# RC_Receive_SCH.net
KiCad netlist of a schematic drawn in Altium Designer
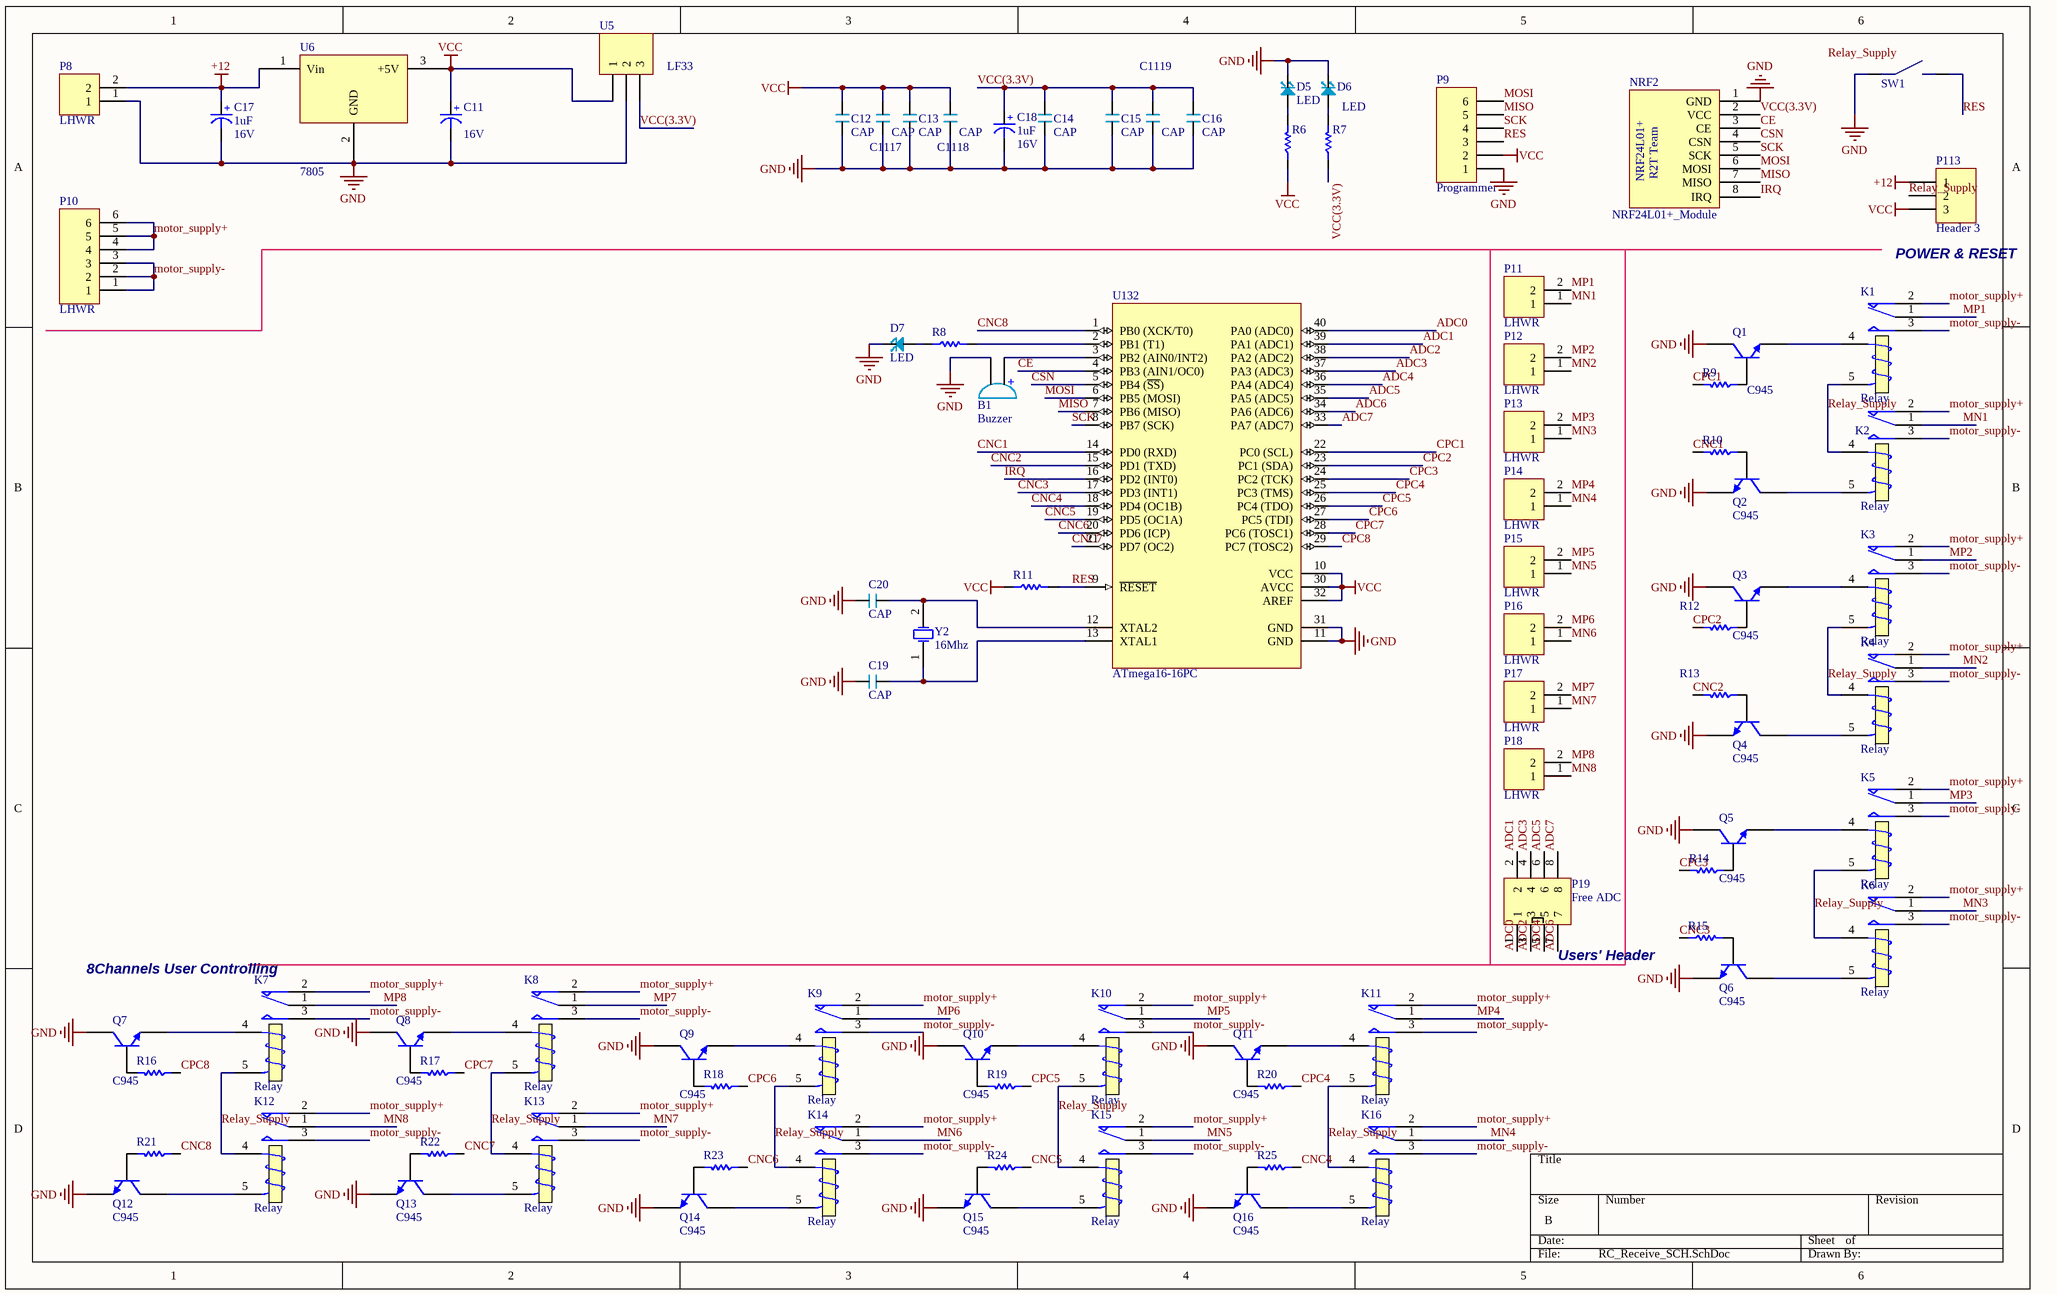
[diagram p0: RC_Receive_SCH.SchDoc]

(export (version "E")
  (design (tool "Eeschema 10.0.6"))
  (components
    (comp (ref "B1")
      (value "Buzzer")
      (footprint "Buzzer")
      (fields (field (name "DESIGNER") "Hamed Jafarzadeh"))
      (libsource (lib "R2T Team Library") (part "Buzzer"))
    )
    (comp (ref "C11")
      (value "~")
      (footprint "cap 01")
      (description "Polar Capacitor")
      (fields (field (name "VOLTAGE") "16V") (field (name "DESIGNER") "Saeid Jorablo"))
      (libsource (lib "My Library") (part "Cap-Polar"))
    )
    (comp (ref "C12") (value "CAP") (footprint "RAD_ADA") (libsource (lib "My_lib_new") (part "CAP")))
    (comp (ref "C13") (value "CAP") (footprint "RAD_ADA") (libsource (lib "My_lib_new") (part "CAP")))
    (comp (ref "C14") (value "CAP") (footprint "RAD_ADA") (libsource (lib "My_lib_new") (part "CAP")))
    (comp (ref "C15") (value "CAP") (footprint "RAD_ADA") (libsource (lib "My_lib_new") (part "CAP")))
    (comp (ref "C16") (value "CAP") (footprint "RAD_ADA") (libsource (lib "My_lib_new") (part "CAP")))
    (comp (ref "C17")
      (value "1uF")
      (footprint "cap 01")
      (description "Polar Capacitor")
      (fields (field (name "VOLTAGE") "16V") (field (name "DESIGNER") "Saeid Jorablo"))
      (libsource (lib "My Library") (part "Cap-Polar"))
    )
    (comp (ref "C18")
      (value "1uF")
      (footprint "cap 01")
      (description "Polar Capacitor")
      (fields (field (name "VOLTAGE") "16V") (field (name "DESIGNER") "Saeid Jorablo"))
      (libsource (lib "My Library") (part "Cap-Polar"))
    )
    (comp (ref "C19") (value "CAP") (footprint "RAD_ADA") (libsource (lib "My_lib_new") (part "CAP")))
    (comp (ref "C20") (value "CAP") (footprint "RAD_ADA") (libsource (lib "My_lib_new") (part "CAP")))
    (comp (ref "C1117") (value "CAP") (footprint "RAD_ADA") (libsource (lib "My_lib_new") (part "CAP")))
    (comp (ref "C1118") (value "CAP") (footprint "RAD_ADA") (libsource (lib "My_lib_new") (part "CAP")))
    (comp (ref "C1119") (value "CAP") (footprint "RAD_ADA") (libsource (lib "My_lib_new") (part "CAP")))
    (comp (ref "D5") (value "LED") (footprint "LED_5MM") (libsource (lib "My_lib_new") (part "LED")))
    (comp (ref "D6") (value "LED") (footprint "LED_5MM") (libsource (lib "My_lib_new") (part "LED")))
    (comp (ref "D7") (value "LED") (footprint "LED_5MM") (libsource (lib "My_lib_new") (part "LED")))
    (comp (ref "K1")
      (value "Relay")
      (footprint "Relay 15.40x12.10x13.10")
      (description "SPDT Relay")
      (fields (field (name "DESIGNER") "Eng. Saeid Jorablo"))
      (libsource (lib "My Library") (part "Relay"))
    )
    (comp (ref "K2")
      (value "Relay")
      (footprint "Relay 15.40x12.10x13.10")
      (description "SPDT Relay")
      (fields (field (name "DESIGNER") "Eng. Saeid Jorablo"))
      (libsource (lib "My Library") (part "Relay"))
    )
    (comp (ref "K3")
      (value "Relay")
      (footprint "Relay 15.40x12.10x13.10")
      (description "SPDT Relay")
      (fields (field (name "DESIGNER") "Eng. Saeid Jorablo"))
      (libsource (lib "My Library") (part "Relay"))
    )
    (comp (ref "K4")
      (value "Relay")
      (footprint "Relay 15.40x12.10x13.10")
      (description "SPDT Relay")
      (fields (field (name "DESIGNER") "Eng. Saeid Jorablo"))
      (libsource (lib "My Library") (part "Relay"))
    )
    (comp (ref "K5")
      (value "Relay")
      (footprint "Relay 15.40x12.10x13.10")
      (description "SPDT Relay")
      (fields (field (name "DESIGNER") "Eng. Saeid Jorablo"))
      (libsource (lib "My Library") (part "Relay"))
    )
    (comp (ref "K6")
      (value "Relay")
      (footprint "Relay 15.40x12.10x13.10")
      (description "SPDT Relay")
      (fields (field (name "DESIGNER") "Eng. Saeid Jorablo"))
      (libsource (lib "My Library") (part "Relay"))
    )
    (comp (ref "K7")
      (value "Relay")
      (footprint "Relay 15.40x12.10x13.10")
      (description "SPDT Relay")
      (fields (field (name "DESIGNER") "Eng. Saeid Jorablo"))
      (libsource (lib "My Library") (part "Relay"))
    )
    (comp (ref "K8")
      (value "Relay")
      (footprint "Relay 15.40x12.10x13.10")
      (description "SPDT Relay")
      (fields (field (name "DESIGNER") "Eng. Saeid Jorablo"))
      (libsource (lib "My Library") (part "Relay"))
    )
    (comp (ref "K9")
      (value "Relay")
      (footprint "Relay 15.40x12.10x13.10")
      (description "SPDT Relay")
      (fields (field (name "DESIGNER") "Eng. Saeid Jorablo"))
      (libsource (lib "My Library") (part "Relay"))
    )
    (comp (ref "K10")
      (value "Relay")
      (footprint "Relay 15.40x12.10x13.10")
      (description "SPDT Relay")
      (fields (field (name "DESIGNER") "Eng. Saeid Jorablo"))
      (libsource (lib "My Library") (part "Relay"))
    )
    (comp (ref "K11")
      (value "Relay")
      (footprint "Relay 15.40x12.10x13.10")
      (description "SPDT Relay")
      (fields (field (name "DESIGNER") "Eng. Saeid Jorablo"))
      (libsource (lib "My Library") (part "Relay"))
    )
    (comp (ref "K12")
      (value "Relay")
      (footprint "Relay 15.40x12.10x13.10")
      (description "SPDT Relay")
      (fields (field (name "DESIGNER") "Eng. Saeid Jorablo"))
      (libsource (lib "My Library") (part "Relay"))
    )
    (comp (ref "K13")
      (value "Relay")
      (footprint "Relay 15.40x12.10x13.10")
      (description "SPDT Relay")
      (fields (field (name "DESIGNER") "Eng. Saeid Jorablo"))
      (libsource (lib "My Library") (part "Relay"))
    )
    (comp (ref "K14")
      (value "Relay")
      (footprint "Relay 15.40x12.10x13.10")
      (description "SPDT Relay")
      (fields (field (name "DESIGNER") "Eng. Saeid Jorablo"))
      (libsource (lib "My Library") (part "Relay"))
    )
    (comp (ref "K15")
      (value "Relay")
      (footprint "Relay 15.40x12.10x13.10")
      (description "SPDT Relay")
      (fields (field (name "DESIGNER") "Eng. Saeid Jorablo"))
      (libsource (lib "My Library") (part "Relay"))
    )
    (comp (ref "K16")
      (value "Relay")
      (footprint "Relay 15.40x12.10x13.10")
      (description "SPDT Relay")
      (fields (field (name "DESIGNER") "Eng. Saeid Jorablo"))
      (libsource (lib "My Library") (part "Relay"))
    )
    (comp (ref "NRF2")
      (value "NRF24L01+_Module")
      (footprint "NRF24L01+_Module")
      (fields (field (name "DESIGNER:") "HamedJafarzadeh"))
      (libsource (lib "R2T Team Library") (part "NRF24L01+_Module"))
    )
    (comp (ref "P8")
      (value "LHWR")
      (footprint "Polarized Header 2")
      (fields (field (name "DESIGNER:") "Hamed Jafarzadeh - www.R2T.ir"))
      (libsource (lib "R2T Team Library") (part "2pin LHWR"))
    )
    (comp (ref "P9")
      (value "Programmer")
      (footprint "HDR1X6")
      (description "Header, 6-Pin")
      (fields (field (name "PUBLISHER") "Altium Limited"))
      (libsource (lib "Miscellaneous Connectors") (part "Header 6"))
    )
    (comp (ref "P10")
      (value "LHWR")
      (footprint "Polarized Header 6")
      (fields (field (name "DESIGNER:") "Hamed Jafarzadeh - www.R2T.ir"))
      (libsource (lib "R2T Team Library") (part "6pin LHWR"))
    )
    (comp (ref "P11")
      (value "LHWR")
      (footprint "Polarized Header 2")
      (fields (field (name "DESIGNER:") "Hamed Jafarzadeh - www.R2T.ir"))
      (libsource (lib "R2T Team Library") (part "2pin LHWR"))
    )
    (comp (ref "P12")
      (value "LHWR")
      (footprint "Polarized Header 2")
      (fields (field (name "DESIGNER:") "Hamed Jafarzadeh - www.R2T.ir"))
      (libsource (lib "R2T Team Library") (part "2pin LHWR"))
    )
    (comp (ref "P13")
      (value "LHWR")
      (footprint "Polarized Header 2")
      (fields (field (name "DESIGNER:") "Hamed Jafarzadeh - www.R2T.ir"))
      (libsource (lib "R2T Team Library") (part "2pin LHWR"))
    )
    (comp (ref "P14")
      (value "LHWR")
      (footprint "Polarized Header 2")
      (fields (field (name "DESIGNER:") "Hamed Jafarzadeh - www.R2T.ir"))
      (libsource (lib "R2T Team Library") (part "2pin LHWR"))
    )
    (comp (ref "P15")
      (value "LHWR")
      (footprint "Polarized Header 2")
      (fields (field (name "DESIGNER:") "Hamed Jafarzadeh - www.R2T.ir"))
      (libsource (lib "R2T Team Library") (part "2pin LHWR"))
    )
    (comp (ref "P16")
      (value "LHWR")
      (footprint "Polarized Header 2")
      (fields (field (name "DESIGNER:") "Hamed Jafarzadeh - www.R2T.ir"))
      (libsource (lib "R2T Team Library") (part "2pin LHWR"))
    )
    (comp (ref "P17")
      (value "LHWR")
      (footprint "Polarized Header 2")
      (fields (field (name "DESIGNER:") "Hamed Jafarzadeh - www.R2T.ir"))
      (libsource (lib "R2T Team Library") (part "2pin LHWR"))
    )
    (comp (ref "P18")
      (value "LHWR")
      (footprint "Polarized Header 2")
      (fields (field (name "DESIGNER:") "Hamed Jafarzadeh - www.R2T.ir"))
      (libsource (lib "R2T Team Library") (part "2pin LHWR"))
    )
    (comp (ref "P19")
      (value "Free ADC")
      (footprint "Box Header 2x4")
      (fields (field (name "DESIGNER") "HamedJafarzadeh - ww.R2T.ir"))
      (libsource (lib "R2T Team Library") (part "BoxHeader 2x4"))
    )
    (comp (ref "P113")
      (value "Header 3")
      (footprint "HDR1X3")
      (description "Header, 3-Pin")
      (fields (field (name "PUBLISHER") "Altium Limited"))
      (libsource (lib "Miscellaneous Connectors") (part "Header 3"))
    )
    (comp (ref "Q1")
      (value "C945")
      (footprint "C945")
      (description "NPN Transistor")
      (fields (field (name "DESIGNER") "Saeid Jorablo"))
      (libsource (lib "My Library") (part "C945"))
    )
    (comp (ref "Q2")
      (value "C945")
      (footprint "C945")
      (description "NPN Transistor")
      (fields (field (name "DESIGNER") "Saeid Jorablo"))
      (libsource (lib "My Library") (part "C945"))
    )
    (comp (ref "Q3")
      (value "C945")
      (footprint "C945")
      (description "NPN Transistor")
      (fields (field (name "DESIGNER") "Saeid Jorablo"))
      (libsource (lib "My Library") (part "C945"))
    )
    (comp (ref "Q4")
      (value "C945")
      (footprint "C945")
      (description "NPN Transistor")
      (fields (field (name "DESIGNER") "Saeid Jorablo"))
      (libsource (lib "My Library") (part "C945"))
    )
    (comp (ref "Q5")
      (value "C945")
      (footprint "C945")
      (description "NPN Transistor")
      (fields (field (name "DESIGNER") "Saeid Jorablo"))
      (libsource (lib "My Library") (part "C945"))
    )
    (comp (ref "Q6")
      (value "C945")
      (footprint "C945")
      (description "NPN Transistor")
      (fields (field (name "DESIGNER") "Saeid Jorablo"))
      (libsource (lib "My Library") (part "C945"))
    )
    (comp (ref "Q7")
      (value "C945")
      (footprint "C945")
      (description "NPN Transistor")
      (fields (field (name "DESIGNER") "Saeid Jorablo"))
      (libsource (lib "My Library") (part "C945"))
    )
    (comp (ref "Q8")
      (value "C945")
      (footprint "C945")
      (description "NPN Transistor")
      (fields (field (name "DESIGNER") "Saeid Jorablo"))
      (libsource (lib "My Library") (part "C945"))
    )
    (comp (ref "Q9")
      (value "C945")
      (footprint "C945")
      (description "NPN Transistor")
      (fields (field (name "DESIGNER") "Saeid Jorablo"))
      (libsource (lib "My Library") (part "C945"))
    )
    (comp (ref "Q10")
      (value "C945")
      (footprint "C945")
      (description "NPN Transistor")
      (fields (field (name "DESIGNER") "Saeid Jorablo"))
      (libsource (lib "My Library") (part "C945"))
    )
    (comp (ref "Q11")
      (value "C945")
      (footprint "C945")
      (description "NPN Transistor")
      (fields (field (name "DESIGNER") "Saeid Jorablo"))
      (libsource (lib "My Library") (part "C945"))
    )
    (comp (ref "Q12")
      (value "C945")
      (footprint "C945")
      (description "NPN Transistor")
      (fields (field (name "DESIGNER") "Saeid Jorablo"))
      (libsource (lib "My Library") (part "C945"))
    )
    (comp (ref "Q13")
      (value "C945")
      (footprint "C945")
      (description "NPN Transistor")
      (fields (field (name "DESIGNER") "Saeid Jorablo"))
      (libsource (lib "My Library") (part "C945"))
    )
    (comp (ref "Q14")
      (value "C945")
      (footprint "C945")
      (description "NPN Transistor")
      (fields (field (name "DESIGNER") "Saeid Jorablo"))
      (libsource (lib "My Library") (part "C945"))
    )
    (comp (ref "Q15")
      (value "C945")
      (footprint "C945")
      (description "NPN Transistor")
      (fields (field (name "DESIGNER") "Saeid Jorablo"))
      (libsource (lib "My Library") (part "C945"))
    )
    (comp (ref "Q16")
      (value "C945")
      (footprint "C945")
      (description "NPN Transistor")
      (fields (field (name "DESIGNER") "Saeid Jorablo"))
      (libsource (lib "My Library") (part "C945"))
    )
    (comp (ref "R6")
      (value "1K")
      (footprint "Res-(1/4)-Stand")
      (description "Resistor")
      (fields (field (name "TOLERANCE") "5%") (field (name "POWER") "1/8 W"))
      (libsource (lib "My Library") (part "Resistor"))
    )
    (comp (ref "R7")
      (value "1K")
      (footprint "Res-(1/4)-Stand")
      (description "Resistor")
      (fields (field (name "TOLERANCE") "5%") (field (name "POWER") "1/8 W"))
      (libsource (lib "My Library") (part "Resistor"))
    )
    (comp (ref "R8")
      (value "1K")
      (footprint "Res-(1/4)-Stand")
      (description "Resistor")
      (fields (field (name "TOLERANCE") "5%") (field (name "POWER") "1/8 W"))
      (libsource (lib "My Library") (part "Resistor"))
    )
    (comp (ref "R9")
      (value "1K")
      (footprint "Res-(1/4)-Stand")
      (description "Resistor")
      (fields (field (name "TOLERANCE") "5%") (field (name "POWER") "1/8 W"))
      (libsource (lib "My Library") (part "Resistor"))
    )
    (comp (ref "R10")
      (value "1K")
      (footprint "Res-(1/4)-Stand")
      (description "Resistor")
      (fields (field (name "TOLERANCE") "5%") (field (name "POWER") "1/8 W"))
      (libsource (lib "My Library") (part "Resistor"))
    )
    (comp (ref "R11")
      (value "1K")
      (footprint "Res-(1/4)-Stand")
      (description "Resistor")
      (fields (field (name "TOLERANCE") "5%") (field (name "POWER") "1/8 W"))
      (libsource (lib "My Library") (part "Resistor"))
    )
    (comp (ref "R12")
      (value "1K")
      (footprint "Res-(1/4)-Stand")
      (description "Resistor")
      (fields (field (name "TOLERANCE") "5%") (field (name "POWER") "1/8 W"))
      (libsource (lib "My Library") (part "Resistor"))
    )
    (comp (ref "R13")
      (value "1K")
      (footprint "Res-(1/4)-Stand")
      (description "Resistor")
      (fields (field (name "TOLERANCE") "5%") (field (name "POWER") "1/8 W"))
      (libsource (lib "My Library") (part "Resistor"))
    )
    (comp (ref "R14")
      (value "1K")
      (footprint "Res-(1/4)-Stand")
      (description "Resistor")
      (fields (field (name "TOLERANCE") "5%") (field (name "POWER") "1/8 W"))
      (libsource (lib "My Library") (part "Resistor"))
    )
    (comp (ref "R15")
      (value "1K")
      (footprint "Res-(1/4)-Stand")
      (description "Resistor")
      (fields (field (name "TOLERANCE") "5%") (field (name "POWER") "1/8 W"))
      (libsource (lib "My Library") (part "Resistor"))
    )
    (comp (ref "R16")
      (value "1K")
      (footprint "Res-(1/4)-Stand")
      (description "Resistor")
      (fields (field (name "TOLERANCE") "5%") (field (name "POWER") "1/8 W"))
      (libsource (lib "My Library") (part "Resistor"))
    )
    (comp (ref "R17")
      (value "1K")
      (footprint "Res-(1/4)-Stand")
      (description "Resistor")
      (fields (field (name "TOLERANCE") "5%") (field (name "POWER") "1/8 W"))
      (libsource (lib "My Library") (part "Resistor"))
    )
    (comp (ref "R18")
      (value "1K")
      (footprint "Res-(1/4)-Stand")
      (description "Resistor")
      (fields (field (name "TOLERANCE") "5%") (field (name "POWER") "1/8 W"))
      (libsource (lib "My Library") (part "Resistor"))
    )
    (comp (ref "R19")
      (value "1K")
      (footprint "Res-(1/4)-Stand")
      (description "Resistor")
      (fields (field (name "TOLERANCE") "5%") (field (name "POWER") "1/8 W"))
      (libsource (lib "My Library") (part "Resistor"))
    )
    (comp (ref "R20")
      (value "1K")
      (footprint "Res-(1/4)-Stand")
      (description "Resistor")
      (fields (field (name "TOLERANCE") "5%") (field (name "POWER") "1/8 W"))
      (libsource (lib "My Library") (part "Resistor"))
    )
    (comp (ref "R21")
      (value "1K")
      (footprint "Res-(1/4)-Stand")
      (description "Resistor")
      (fields (field (name "TOLERANCE") "5%") (field (name "POWER") "1/8 W"))
      (libsource (lib "My Library") (part "Resistor"))
    )
    (comp (ref "R22")
      (value "1K")
      (footprint "Res-(1/4)-Stand")
      (description "Resistor")
      (fields (field (name "TOLERANCE") "5%") (field (name "POWER") "1/8 W"))
      (libsource (lib "My Library") (part "Resistor"))
    )
    (comp (ref "R23")
      (value "1K")
      (footprint "Res-(1/4)-Stand")
      (description "Resistor")
      (fields (field (name "TOLERANCE") "5%") (field (name "POWER") "1/8 W"))
      (libsource (lib "My Library") (part "Resistor"))
    )
    (comp (ref "R24")
      (value "1K")
      (footprint "Res-(1/4)-Stand")
      (description "Resistor")
      (fields (field (name "TOLERANCE") "5%") (field (name "POWER") "1/8 W"))
      (libsource (lib "My Library") (part "Resistor"))
    )
    (comp (ref "R25")
      (value "1K")
      (footprint "Res-(1/4)-Stand")
      (description "Resistor")
      (fields (field (name "TOLERANCE") "5%") (field (name "POWER") "1/8 W"))
      (libsource (lib "My Library") (part "Resistor"))
    )
    (comp (ref "SW1") (value "SWITCH") (footprint "SWITCH") (libsource (lib "SPLib") (part "SWITCH")))
    (comp (ref "U5")
      (value "LF33")
      (footprint "HDR1X3")
      (description "Header, 3-Pin")
      (fields (field (name "PUBLISHER") "Altium Limited"))
      (libsource (lib "") (part "Header 3_1"))
    )
    (comp (ref "U6")
      (value "7805")
      (footprint "My_TO-220")
      (description "Regulator")
      (libsource (lib "Mylib") (part "7805"))
    )
    (comp (ref "U132")
      (value "ATmega16-16PC")
      (footprint "40P6")
      (description "8-Bit AVR Microcontroller with 16K Bytes of In-System Programmable Flash Memory")
      (fields (field (name "PUBLISHER") "Altium Limited"))
      (libsource (lib "Atmel Microcontroller 8-Bit AVR") (part "ATmega16-16PC"))
    )
    (comp (ref "Y2")
      (value "16Mhz")
      (footprint "XTAL Small")
      (description "XTAL Crystal")
      (libsource (lib "My Library") (part "XTAL"))
    )
  )
  (nets
    (net (code "1") (name "+12") (class "Default")
      (node (ref "C17") (pin "1") (pinfunction "+_1") (pintype "passive"))
      (node (ref "P113") (pin "1") (pinfunction "1_1") (pintype "passive"))
      (node (ref "P8") (pin "2") (pinfunction "2_2") (pintype "passive"))
      (node (ref "U6") (pin "1") (pinfunction "Vin_1") (pintype "power_in"))
    )
    (net (code "2") (name "/ADC0") (class "Default")
      (node (ref "P19") (pin "1") (pinfunction "1_1") (pintype "passive"))
      (node (ref "U132") (pin "40") (pinfunction "PA0_(ADC0)_40") (pintype "bidirectional"))
    )
    (net (code "3") (name "/ADC1") (class "Default")
      (node (ref "P19") (pin "2") (pinfunction "2_2") (pintype "passive"))
      (node (ref "U132") (pin "39") (pinfunction "PA1_(ADC1)_39") (pintype "bidirectional"))
    )
    (net (code "4") (name "/ADC2") (class "Default")
      (node (ref "P19") (pin "3") (pinfunction "3_3") (pintype "passive"))
      (node (ref "U132") (pin "38") (pinfunction "PA2_(ADC2)_38") (pintype "bidirectional"))
    )
    (net (code "5") (name "/ADC3") (class "Default")
      (node (ref "P19") (pin "4") (pinfunction "4_4") (pintype "passive"))
      (node (ref "U132") (pin "37") (pinfunction "PA3_(ADC3)_37") (pintype "bidirectional"))
    )
    (net (code "6") (name "/ADC4") (class "Default")
      (node (ref "P19") (pin "5") (pinfunction "5_5") (pintype "passive"))
      (node (ref "U132") (pin "36") (pinfunction "PA4_(ADC4)_36") (pintype "bidirectional"))
    )
    (net (code "7") (name "/ADC5") (class "Default")
      (node (ref "P19") (pin "6") (pinfunction "6_6") (pintype "passive"))
      (node (ref "U132") (pin "35") (pinfunction "PA5_(ADC5)_35") (pintype "bidirectional"))
    )
    (net (code "8") (name "/ADC6") (class "Default")
      (node (ref "P19") (pin "7") (pinfunction "7_7") (pintype "passive"))
      (node (ref "U132") (pin "34") (pinfunction "PA6_(ADC6)_34") (pintype "bidirectional"))
    )
    (net (code "9") (name "/ADC7") (class "Default")
      (node (ref "P19") (pin "8") (pinfunction "8_8") (pintype "passive"))
      (node (ref "U132") (pin "33") (pinfunction "PA7_(ADC7)_33") (pintype "bidirectional"))
    )
    (net (code "10") (name "/CE") (class "Default")
      (node (ref "NRF2") (pin "3") (pinfunction "CE_3") (pintype "passive"))
      (node (ref "U132") (pin "4") (pinfunction "PB3_(AIN1/OC0)_4") (pintype "bidirectional"))
    )
    (net (code "11") (name "/CNC1") (class "Default")
      (node (ref "R10") (pin "2") (pinfunction "2_2") (pintype "passive"))
      (node (ref "U132") (pin "14") (pinfunction "PD0_(RXD)_14") (pintype "bidirectional"))
    )
    (net (code "12") (name "/CNC2") (class "Default")
      (node (ref "R13") (pin "2") (pinfunction "2_2") (pintype "passive"))
      (node (ref "U132") (pin "15") (pinfunction "PD1_(TXD)_15") (pintype "bidirectional"))
    )
    (net (code "13") (name "/CNC3") (class "Default")
      (node (ref "R15") (pin "1") (pinfunction "1_1") (pintype "passive"))
      (node (ref "U132") (pin "17") (pinfunction "PD3_(INT1)_17") (pintype "bidirectional"))
    )
    (net (code "14") (name "/CNC4") (class "Default")
      (node (ref "R25") (pin "1") (pinfunction "1_1") (pintype "passive"))
      (node (ref "U132") (pin "18") (pinfunction "PD4_(OC1B)_18") (pintype "bidirectional"))
    )
    (net (code "15") (name "/CNC5") (class "Default")
      (node (ref "R24") (pin "1") (pinfunction "1_1") (pintype "passive"))
      (node (ref "U132") (pin "19") (pinfunction "PD5_(OC1A)_19") (pintype "bidirectional"))
    )
    (net (code "16") (name "/CNC6") (class "Default")
      (node (ref "R23") (pin "1") (pinfunction "1_1") (pintype "passive"))
      (node (ref "U132") (pin "20") (pinfunction "PD6_(ICP)_20") (pintype "bidirectional"))
    )
    (net (code "17") (name "/CNC7") (class "Default")
      (node (ref "R22") (pin "1") (pinfunction "1_1") (pintype "passive"))
      (node (ref "U132") (pin "21") (pinfunction "PD7_(OC2)_21") (pintype "bidirectional"))
    )
    (net (code "18") (name "/CNC8") (class "Default")
      (node (ref "R21") (pin "1") (pinfunction "1_1") (pintype "passive"))
      (node (ref "U132") (pin "1") (pinfunction "PB0_(XCK/T0)_1") (pintype "bidirectional"))
    )
    (net (code "19") (name "/CPC1") (class "Default")
      (node (ref "R9") (pin "2") (pinfunction "2_2") (pintype "passive"))
      (node (ref "U132") (pin "22") (pinfunction "PC0_(SCL)_22") (pintype "bidirectional"))
    )
    (net (code "20") (name "/CPC2") (class "Default")
      (node (ref "R12") (pin "2") (pinfunction "2_2") (pintype "passive"))
      (node (ref "U132") (pin "23") (pinfunction "PC1_(SDA)_23") (pintype "bidirectional"))
    )
    (net (code "21") (name "/CPC3") (class "Default")
      (node (ref "R14") (pin "2") (pinfunction "2_2") (pintype "passive"))
      (node (ref "U132") (pin "24") (pinfunction "PC2_(TCK)_24") (pintype "bidirectional"))
    )
    (net (code "22") (name "/CPC4") (class "Default")
      (node (ref "R20") (pin "1") (pinfunction "1_1") (pintype "passive"))
      (node (ref "U132") (pin "25") (pinfunction "PC3_(TMS)_25") (pintype "bidirectional"))
    )
    (net (code "23") (name "/CPC5") (class "Default")
      (node (ref "R19") (pin "1") (pinfunction "1_1") (pintype "passive"))
      (node (ref "U132") (pin "26") (pinfunction "PC4_(TDO)_26") (pintype "bidirectional"))
    )
    (net (code "24") (name "/CPC6") (class "Default")
      (node (ref "R18") (pin "1") (pinfunction "1_1") (pintype "passive"))
      (node (ref "U132") (pin "27") (pinfunction "PC5_(TDI)_27") (pintype "bidirectional"))
    )
    (net (code "25") (name "/CPC7") (class "Default")
      (node (ref "R17") (pin "1") (pinfunction "1_1") (pintype "passive"))
      (node (ref "U132") (pin "28") (pinfunction "PC6_(TOSC1)_28") (pintype "bidirectional"))
    )
    (net (code "26") (name "/CPC8") (class "Default")
      (node (ref "R16") (pin "1") (pinfunction "1_1") (pintype "passive"))
      (node (ref "U132") (pin "29") (pinfunction "PC7_(TOSC2)_29") (pintype "bidirectional"))
    )
    (net (code "27") (name "/CSN") (class "Default")
      (node (ref "NRF2") (pin "4") (pinfunction "CSN_4") (pintype "passive"))
      (node (ref "U132") (pin "5") (pinfunction "PB4_(~{SS})_5") (pintype "bidirectional"))
    )
    (net (code "28") (name "/IRQ") (class "Default")
      (node (ref "NRF2") (pin "8") (pinfunction "IRQ_8") (pintype "passive"))
      (node (ref "U132") (pin "16") (pinfunction "PD2_(INT0)_16") (pintype "bidirectional"))
    )
    (net (code "29") (name "/MISO") (class "Default")
      (node (ref "NRF2") (pin "7") (pinfunction "MISO_7") (pintype "passive"))
      (node (ref "P9") (pin "5") (pinfunction "5_5") (pintype "passive"))
      (node (ref "U132") (pin "7") (pinfunction "PB6_(MISO)_7") (pintype "bidirectional"))
    )
    (net (code "30") (name "/MN1") (class "Default")
      (node (ref "K2") (pin "1") (pinfunction "COM_1") (pintype "passive"))
      (node (ref "P11") (pin "1") (pinfunction "1_1") (pintype "passive"))
    )
    (net (code "31") (name "/MN2") (class "Default")
      (node (ref "K4") (pin "1") (pinfunction "COM_1") (pintype "passive"))
      (node (ref "P12") (pin "1") (pinfunction "1_1") (pintype "passive"))
    )
    (net (code "32") (name "/MN3") (class "Default")
      (node (ref "K6") (pin "1") (pinfunction "COM_1") (pintype "passive"))
      (node (ref "P13") (pin "1") (pinfunction "1_1") (pintype "passive"))
    )
    (net (code "33") (name "/MN4") (class "Default")
      (node (ref "K16") (pin "1") (pinfunction "COM_1") (pintype "passive"))
      (node (ref "P14") (pin "1") (pinfunction "1_1") (pintype "passive"))
    )
    (net (code "34") (name "/MN5") (class "Default")
      (node (ref "K15") (pin "1") (pinfunction "COM_1") (pintype "passive"))
      (node (ref "P15") (pin "1") (pinfunction "1_1") (pintype "passive"))
    )
    (net (code "35") (name "/MN6") (class "Default")
      (node (ref "K14") (pin "1") (pinfunction "COM_1") (pintype "passive"))
      (node (ref "P16") (pin "1") (pinfunction "1_1") (pintype "passive"))
    )
    (net (code "36") (name "/MN7") (class "Default")
      (node (ref "K13") (pin "1") (pinfunction "COM_1") (pintype "passive"))
      (node (ref "P17") (pin "1") (pinfunction "1_1") (pintype "passive"))
    )
    (net (code "37") (name "/MN8") (class "Default")
      (node (ref "K12") (pin "1") (pinfunction "COM_1") (pintype "passive"))
      (node (ref "P18") (pin "1") (pinfunction "1_1") (pintype "passive"))
    )
    (net (code "38") (name "/MOSI") (class "Default")
      (node (ref "NRF2") (pin "6") (pinfunction "MOSI_6") (pintype "passive"))
      (node (ref "P9") (pin "6") (pinfunction "6_6") (pintype "passive"))
      (node (ref "U132") (pin "6") (pinfunction "PB5_(MOSI)_6") (pintype "bidirectional"))
    )
    (net (code "39") (name "/MP1") (class "Default")
      (node (ref "K1") (pin "1") (pinfunction "COM_1") (pintype "passive"))
      (node (ref "P11") (pin "2") (pinfunction "2_2") (pintype "passive"))
    )
    (net (code "40") (name "/MP2") (class "Default")
      (node (ref "K3") (pin "1") (pinfunction "COM_1") (pintype "passive"))
      (node (ref "P12") (pin "2") (pinfunction "2_2") (pintype "passive"))
    )
    (net (code "41") (name "/MP3") (class "Default")
      (node (ref "K5") (pin "1") (pinfunction "COM_1") (pintype "passive"))
      (node (ref "P13") (pin "2") (pinfunction "2_2") (pintype "passive"))
    )
    (net (code "42") (name "/MP4") (class "Default")
      (node (ref "K11") (pin "1") (pinfunction "COM_1") (pintype "passive"))
      (node (ref "P14") (pin "2") (pinfunction "2_2") (pintype "passive"))
    )
    (net (code "43") (name "/MP5") (class "Default")
      (node (ref "K10") (pin "1") (pinfunction "COM_1") (pintype "passive"))
      (node (ref "P15") (pin "2") (pinfunction "2_2") (pintype "passive"))
    )
    (net (code "44") (name "/MP6") (class "Default")
      (node (ref "K9") (pin "1") (pinfunction "COM_1") (pintype "passive"))
      (node (ref "P16") (pin "2") (pinfunction "2_2") (pintype "passive"))
    )
    (net (code "45") (name "/MP7") (class "Default")
      (node (ref "K8") (pin "1") (pinfunction "COM_1") (pintype "passive"))
      (node (ref "P17") (pin "2") (pinfunction "2_2") (pintype "passive"))
    )
    (net (code "46") (name "/MP8") (class "Default")
      (node (ref "K7") (pin "1") (pinfunction "COM_1") (pintype "passive"))
      (node (ref "P18") (pin "2") (pinfunction "2_2") (pintype "passive"))
    )
    (net (code "47") (name "/RES") (class "Default")
      (node (ref "P9") (pin "3") (pinfunction "3_3") (pintype "passive"))
      (node (ref "R11") (pin "2") (pinfunction "2_2") (pintype "passive"))
      (node (ref "SW1") (pin "2") (pinfunction "2_2") (pintype "passive"))
      (node (ref "U132") (pin "9") (pinfunction "~{RESET}_9") (pintype "input"))
    )
    (net (code "48") (name "/Relay_Supply") (class "Default")
      (node (ref "K1") (pin "5") (pinfunction "T2_5") (pintype "passive"))
      (node (ref "K10") (pin "5") (pinfunction "T2_5") (pintype "passive"))
      (node (ref "K11") (pin "5") (pinfunction "T2_5") (pintype "passive"))
      (node (ref "K12") (pin "4") (pinfunction "T1_4") (pintype "passive"))
      (node (ref "K13") (pin "4") (pinfunction "T1_4") (pintype "passive"))
      (node (ref "K14") (pin "4") (pinfunction "T1_4") (pintype "passive"))
      (node (ref "K15") (pin "4") (pinfunction "T1_4") (pintype "passive"))
      (node (ref "K16") (pin "4") (pinfunction "T1_4") (pintype "passive"))
      (node (ref "K2") (pin "4") (pinfunction "T1_4") (pintype "passive"))
      (node (ref "K3") (pin "5") (pinfunction "T2_5") (pintype "passive"))
      (node (ref "K4") (pin "4") (pinfunction "T1_4") (pintype "passive"))
      (node (ref "K5") (pin "5") (pinfunction "T2_5") (pintype "passive"))
      (node (ref "K6") (pin "4") (pinfunction "T1_4") (pintype "passive"))
      (node (ref "K7") (pin "5") (pinfunction "T2_5") (pintype "passive"))
      (node (ref "K8") (pin "5") (pinfunction "T2_5") (pintype "passive"))
      (node (ref "K9") (pin "5") (pinfunction "T2_5") (pintype "passive"))
      (node (ref "P113") (pin "2") (pinfunction "2_2") (pintype "passive"))
    )
    (net (code "49") (name "/SCK") (class "Default")
      (node (ref "NRF2") (pin "5") (pinfunction "SCK_5") (pintype "passive"))
      (node (ref "P9") (pin "4") (pinfunction "4_4") (pintype "passive"))
      (node (ref "U132") (pin "8") (pinfunction "PB7_(SCK)_8") (pintype "bidirectional"))
    )
    (net (code "50") (name "/VCC(3.3V)") (class "Default")
      (node (ref "C1119") (pin "2") (pintype "passive"))
      (node (ref "C14") (pin "2") (pintype "passive"))
      (node (ref "C15") (pin "2") (pintype "passive"))
      (node (ref "C16") (pin "2") (pintype "passive"))
      (node (ref "C18") (pin "1") (pinfunction "+_1") (pintype "passive"))
      (node (ref "NRF2") (pin "2") (pinfunction "VCC_2") (pintype "passive"))
      (node (ref "R7") (pin "1") (pinfunction "1_1") (pintype "passive"))
      (node (ref "U5") (pin "3") (pinfunction "3_3") (pintype "passive"))
    )
    (net (code "51") (name "/motor_supply+") (class "Default")
      (node (ref "K1") (pin "2") (pinfunction "NC_2") (pintype "passive"))
      (node (ref "K10") (pin "2") (pinfunction "NC_2") (pintype "passive"))
      (node (ref "K11") (pin "2") (pinfunction "NC_2") (pintype "passive"))
      (node (ref "K12") (pin "2") (pinfunction "NC_2") (pintype "passive"))
      (node (ref "K13") (pin "2") (pinfunction "NC_2") (pintype "passive"))
      (node (ref "K14") (pin "2") (pinfunction "NC_2") (pintype "passive"))
      (node (ref "K15") (pin "2") (pinfunction "NC_2") (pintype "passive"))
      (node (ref "K16") (pin "2") (pinfunction "NC_2") (pintype "passive"))
      (node (ref "K2") (pin "2") (pinfunction "NC_2") (pintype "passive"))
      (node (ref "K3") (pin "2") (pinfunction "NC_2") (pintype "passive"))
      (node (ref "K4") (pin "2") (pinfunction "NC_2") (pintype "passive"))
      (node (ref "K5") (pin "2") (pinfunction "NC_2") (pintype "passive"))
      (node (ref "K6") (pin "2") (pinfunction "NC_2") (pintype "passive"))
      (node (ref "K7") (pin "2") (pinfunction "NC_2") (pintype "passive"))
      (node (ref "K8") (pin "2") (pinfunction "NC_2") (pintype "passive"))
      (node (ref "K9") (pin "2") (pinfunction "NC_2") (pintype "passive"))
      (node (ref "P10") (pin "4") (pinfunction "4_4") (pintype "passive"))
      (node (ref "P10") (pin "5") (pinfunction "5_5") (pintype "passive"))
      (node (ref "P10") (pin "6") (pinfunction "6_6") (pintype "passive"))
    )
    (net (code "52") (name "/motor_supply-") (class "Default")
      (node (ref "K1") (pin "3") (pinfunction "NO_3") (pintype "passive"))
      (node (ref "K10") (pin "3") (pinfunction "NO_3") (pintype "passive"))
      (node (ref "K11") (pin "3") (pinfunction "NO_3") (pintype "passive"))
      (node (ref "K12") (pin "3") (pinfunction "NO_3") (pintype "passive"))
      (node (ref "K13") (pin "3") (pinfunction "NO_3") (pintype "passive"))
      (node (ref "K14") (pin "3") (pinfunction "NO_3") (pintype "passive"))
      (node (ref "K15") (pin "3") (pinfunction "NO_3") (pintype "passive"))
      (node (ref "K16") (pin "3") (pinfunction "NO_3") (pintype "passive"))
      (node (ref "K2") (pin "3") (pinfunction "NO_3") (pintype "passive"))
      (node (ref "K3") (pin "3") (pinfunction "NO_3") (pintype "passive"))
      (node (ref "K4") (pin "3") (pinfunction "NO_3") (pintype "passive"))
      (node (ref "K5") (pin "3") (pinfunction "NO_3") (pintype "passive"))
      (node (ref "K6") (pin "3") (pinfunction "NO_3") (pintype "passive"))
      (node (ref "K7") (pin "3") (pinfunction "NO_3") (pintype "passive"))
      (node (ref "K8") (pin "3") (pinfunction "NO_3") (pintype "passive"))
      (node (ref "K9") (pin "3") (pinfunction "NO_3") (pintype "passive"))
      (node (ref "P10") (pin "1") (pinfunction "1_1") (pintype "passive"))
      (node (ref "P10") (pin "2") (pinfunction "2_2") (pintype "passive"))
      (node (ref "P10") (pin "3") (pinfunction "3_3") (pintype "passive"))
    )
    (net (code "53") (name "GND") (class "Default")
      (node (ref "B1") (pin "2") (pinfunction "GND_2") (pintype "passive"))
      (node (ref "C11") (pin "2") (pinfunction "-_2") (pintype "passive"))
      (node (ref "C1117") (pin "1") (pintype "passive"))
      (node (ref "C1118") (pin "1") (pintype "passive"))
      (node (ref "C1119") (pin "1") (pintype "passive"))
      (node (ref "C12") (pin "1") (pintype "passive"))
      (node (ref "C13") (pin "1") (pintype "passive"))
      (node (ref "C14") (pin "1") (pintype "passive"))
      (node (ref "C15") (pin "1") (pintype "passive"))
      (node (ref "C16") (pin "1") (pintype "passive"))
      (node (ref "C17") (pin "2") (pinfunction "-_2") (pintype "passive"))
      (node (ref "C18") (pin "2") (pinfunction "-_2") (pintype "passive"))
      (node (ref "C19") (pin "1") (pintype "passive"))
      (node (ref "C20") (pin "2") (pintype "passive"))
      (node (ref "D5") (pin "2") (pintype "passive"))
      (node (ref "D6") (pin "2") (pintype "passive"))
      (node (ref "D7") (pin "2") (pintype "passive"))
      (node (ref "NRF2") (pin "1") (pinfunction "GND_1") (pintype "passive"))
      (node (ref "P8") (pin "1") (pinfunction "1_1") (pintype "passive"))
      (node (ref "P9") (pin "1") (pinfunction "1_1") (pintype "passive"))
      (node (ref "Q1") (pin "2") (pinfunction "C_2") (pintype "passive"))
      (node (ref "Q10") (pin "2") (pinfunction "C_2") (pintype "passive"))
      (node (ref "Q11") (pin "2") (pinfunction "C_2") (pintype "passive"))
      (node (ref "Q12") (pin "1") (pinfunction "E_1") (pintype "passive"))
      (node (ref "Q13") (pin "1") (pinfunction "E_1") (pintype "passive"))
      (node (ref "Q14") (pin "1") (pinfunction "E_1") (pintype "passive"))
      (node (ref "Q15") (pin "1") (pinfunction "E_1") (pintype "passive"))
      (node (ref "Q16") (pin "1") (pinfunction "E_1") (pintype "passive"))
      (node (ref "Q2") (pin "1") (pinfunction "E_1") (pintype "passive"))
      (node (ref "Q3") (pin "2") (pinfunction "C_2") (pintype "passive"))
      (node (ref "Q4") (pin "1") (pinfunction "E_1") (pintype "passive"))
      (node (ref "Q5") (pin "2") (pinfunction "C_2") (pintype "passive"))
      (node (ref "Q6") (pin "1") (pinfunction "E_1") (pintype "passive"))
      (node (ref "Q7") (pin "2") (pinfunction "C_2") (pintype "passive"))
      (node (ref "Q8") (pin "2") (pinfunction "C_2") (pintype "passive"))
      (node (ref "Q9") (pin "2") (pinfunction "C_2") (pintype "passive"))
      (node (ref "SW1") (pin "1") (pinfunction "1_1") (pintype "passive"))
      (node (ref "U132") (pin "11") (pinfunction "GND_11") (pintype "power_in"))
      (node (ref "U132") (pin "31") (pinfunction "GND_31") (pintype "power_in"))
      (node (ref "U5") (pin "2") (pinfunction "2_2") (pintype "passive"))
      (node (ref "U6") (pin "2") (pinfunction "GND_2") (pintype "power_in"))
    )
    (net (code "54") (name "Net-(B1-VCC)") (class "Default")
      (node (ref "B1") (pin "1") (pinfunction "VCC_1") (pintype "passive"))
      (node (ref "U132") (pin "3") (pinfunction "PB2_(AIN0/INT2)_3") (pintype "bidirectional"))
    )
    (net (code "55") (name "Net-(D5-Pad1)") (class "Default")
      (node (ref "D5") (pin "1") (pintype "passive"))
      (node (ref "R6") (pin "2") (pinfunction "2_2") (pintype "passive"))
    )
    (net (code "56") (name "Net-(D6-Pad1)") (class "Default")
      (node (ref "D6") (pin "1") (pintype "passive"))
      (node (ref "R7") (pin "2") (pinfunction "2_2") (pintype "passive"))
    )
    (net (code "57") (name "Net-(D7-Pad1)") (class "Default")
      (node (ref "D7") (pin "1") (pintype "passive"))
      (node (ref "R8") (pin "1") (pinfunction "1_1") (pintype "passive"))
    )
    (net (code "58") (name "Net-(K1-T1)") (class "Default")
      (node (ref "K1") (pin "4") (pinfunction "T1_4") (pintype "passive"))
      (node (ref "Q1") (pin "1") (pinfunction "E_1") (pintype "passive"))
    )
    (net (code "59") (name "Net-(K2-T2)") (class "Default")
      (node (ref "K2") (pin "5") (pinfunction "T2_5") (pintype "passive"))
      (node (ref "Q2") (pin "2") (pinfunction "C_2") (pintype "passive"))
    )
    (net (code "60") (name "Net-(K3-T1)") (class "Default")
      (node (ref "K3") (pin "4") (pinfunction "T1_4") (pintype "passive"))
      (node (ref "Q3") (pin "1") (pinfunction "E_1") (pintype "passive"))
    )
    (net (code "61") (name "Net-(K4-T2)") (class "Default")
      (node (ref "K4") (pin "5") (pinfunction "T2_5") (pintype "passive"))
      (node (ref "Q4") (pin "2") (pinfunction "C_2") (pintype "passive"))
    )
    (net (code "62") (name "Net-(K5-T1)") (class "Default")
      (node (ref "K5") (pin "4") (pinfunction "T1_4") (pintype "passive"))
      (node (ref "Q5") (pin "1") (pinfunction "E_1") (pintype "passive"))
    )
    (net (code "63") (name "Net-(K6-T2)") (class "Default")
      (node (ref "K6") (pin "5") (pinfunction "T2_5") (pintype "passive"))
      (node (ref "Q6") (pin "2") (pinfunction "C_2") (pintype "passive"))
    )
    (net (code "64") (name "Net-(K7-T1)") (class "Default")
      (node (ref "K7") (pin "4") (pinfunction "T1_4") (pintype "passive"))
      (node (ref "Q7") (pin "1") (pinfunction "E_1") (pintype "passive"))
    )
    (net (code "65") (name "Net-(K8-T1)") (class "Default")
      (node (ref "K8") (pin "4") (pinfunction "T1_4") (pintype "passive"))
      (node (ref "Q8") (pin "1") (pinfunction "E_1") (pintype "passive"))
    )
    (net (code "66") (name "Net-(K9-T1)") (class "Default")
      (node (ref "K9") (pin "4") (pinfunction "T1_4") (pintype "passive"))
      (node (ref "Q9") (pin "1") (pinfunction "E_1") (pintype "passive"))
    )
    (net (code "67") (name "Net-(K10-T1)") (class "Default")
      (node (ref "K10") (pin "4") (pinfunction "T1_4") (pintype "passive"))
      (node (ref "Q10") (pin "1") (pinfunction "E_1") (pintype "passive"))
    )
    (net (code "68") (name "Net-(K11-T1)") (class "Default")
      (node (ref "K11") (pin "4") (pinfunction "T1_4") (pintype "passive"))
      (node (ref "Q11") (pin "1") (pinfunction "E_1") (pintype "passive"))
    )
    (net (code "69") (name "Net-(K12-T2)") (class "Default")
      (node (ref "K12") (pin "5") (pinfunction "T2_5") (pintype "passive"))
      (node (ref "Q12") (pin "2") (pinfunction "C_2") (pintype "passive"))
    )
    (net (code "70") (name "Net-(K13-T2)") (class "Default")
      (node (ref "K13") (pin "5") (pinfunction "T2_5") (pintype "passive"))
      (node (ref "Q13") (pin "2") (pinfunction "C_2") (pintype "passive"))
    )
    (net (code "71") (name "Net-(K14-T2)") (class "Default")
      (node (ref "K14") (pin "5") (pinfunction "T2_5") (pintype "passive"))
      (node (ref "Q14") (pin "2") (pinfunction "C_2") (pintype "passive"))
    )
    (net (code "72") (name "Net-(K15-T2)") (class "Default")
      (node (ref "K15") (pin "5") (pinfunction "T2_5") (pintype "passive"))
      (node (ref "Q15") (pin "2") (pinfunction "C_2") (pintype "passive"))
    )
    (net (code "73") (name "Net-(K16-T2)") (class "Default")
      (node (ref "K16") (pin "5") (pinfunction "T2_5") (pintype "passive"))
      (node (ref "Q16") (pin "2") (pinfunction "C_2") (pintype "passive"))
    )
    (net (code "74") (name "Net-(Q1-B)") (class "Default")
      (node (ref "Q1") (pin "3") (pinfunction "B_3") (pintype "passive"))
      (node (ref "R9") (pin "1") (pinfunction "1_1") (pintype "passive"))
    )
    (net (code "75") (name "Net-(Q2-B)") (class "Default")
      (node (ref "Q2") (pin "3") (pinfunction "B_3") (pintype "passive"))
      (node (ref "R10") (pin "1") (pinfunction "1_1") (pintype "passive"))
    )
    (net (code "76") (name "Net-(Q3-B)") (class "Default")
      (node (ref "Q3") (pin "3") (pinfunction "B_3") (pintype "passive"))
      (node (ref "R12") (pin "1") (pinfunction "1_1") (pintype "passive"))
    )
    (net (code "77") (name "Net-(Q4-B)") (class "Default")
      (node (ref "Q4") (pin "3") (pinfunction "B_3") (pintype "passive"))
      (node (ref "R13") (pin "1") (pinfunction "1_1") (pintype "passive"))
    )
    (net (code "78") (name "Net-(Q5-B)") (class "Default")
      (node (ref "Q5") (pin "3") (pinfunction "B_3") (pintype "passive"))
      (node (ref "R14") (pin "1") (pinfunction "1_1") (pintype "passive"))
    )
    (net (code "79") (name "Net-(Q6-B)") (class "Default")
      (node (ref "Q6") (pin "3") (pinfunction "B_3") (pintype "passive"))
      (node (ref "R15") (pin "2") (pinfunction "2_2") (pintype "passive"))
    )
    (net (code "80") (name "Net-(Q7-B)") (class "Default")
      (node (ref "Q7") (pin "3") (pinfunction "B_3") (pintype "passive"))
      (node (ref "R16") (pin "2") (pinfunction "2_2") (pintype "passive"))
    )
    (net (code "81") (name "Net-(Q8-B)") (class "Default")
      (node (ref "Q8") (pin "3") (pinfunction "B_3") (pintype "passive"))
      (node (ref "R17") (pin "2") (pinfunction "2_2") (pintype "passive"))
    )
    (net (code "82") (name "Net-(Q9-B)") (class "Default")
      (node (ref "Q9") (pin "3") (pinfunction "B_3") (pintype "passive"))
      (node (ref "R18") (pin "2") (pinfunction "2_2") (pintype "passive"))
    )
    (net (code "83") (name "Net-(Q10-B)") (class "Default")
      (node (ref "Q10") (pin "3") (pinfunction "B_3") (pintype "passive"))
      (node (ref "R19") (pin "2") (pinfunction "2_2") (pintype "passive"))
    )
    (net (code "84") (name "Net-(Q11-B)") (class "Default")
      (node (ref "Q11") (pin "3") (pinfunction "B_3") (pintype "passive"))
      (node (ref "R20") (pin "2") (pinfunction "2_2") (pintype "passive"))
    )
    (net (code "85") (name "Net-(Q12-B)") (class "Default")
      (node (ref "Q12") (pin "3") (pinfunction "B_3") (pintype "passive"))
      (node (ref "R21") (pin "2") (pinfunction "2_2") (pintype "passive"))
    )
    (net (code "86") (name "Net-(Q13-B)") (class "Default")
      (node (ref "Q13") (pin "3") (pinfunction "B_3") (pintype "passive"))
      (node (ref "R22") (pin "2") (pinfunction "2_2") (pintype "passive"))
    )
    (net (code "87") (name "Net-(Q14-B)") (class "Default")
      (node (ref "Q14") (pin "3") (pinfunction "B_3") (pintype "passive"))
      (node (ref "R23") (pin "2") (pinfunction "2_2") (pintype "passive"))
    )
    (net (code "88") (name "Net-(Q15-B)") (class "Default")
      (node (ref "Q15") (pin "3") (pinfunction "B_3") (pintype "passive"))
      (node (ref "R24") (pin "2") (pinfunction "2_2") (pintype "passive"))
    )
    (net (code "89") (name "Net-(Q16-B)") (class "Default")
      (node (ref "Q16") (pin "3") (pinfunction "B_3") (pintype "passive"))
      (node (ref "R25") (pin "2") (pinfunction "2_2") (pintype "passive"))
    )
    (net (code "90") (name "Net-(U132-PB1_(T1))") (class "Default")
      (node (ref "R8") (pin "2") (pinfunction "2_2") (pintype "passive"))
      (node (ref "U132") (pin "2") (pinfunction "PB1_(T1)_2") (pintype "bidirectional"))
    )
    (net (code "91") (name "Net-(U132-XTAL1)") (class "Default")
      (node (ref "C19") (pin "2") (pintype "passive"))
      (node (ref "U132") (pin "13") (pinfunction "XTAL1_13") (pintype "passive"))
      (node (ref "Y2") (pin "1") (pinfunction "OSC1_1") (pintype "passive"))
    )
    (net (code "92") (name "Net-(U132-XTAL2)") (class "Default")
      (node (ref "C20") (pin "1") (pintype "passive"))
      (node (ref "U132") (pin "12") (pinfunction "XTAL2_12") (pintype "passive"))
      (node (ref "Y2") (pin "2") (pinfunction "OSC2_2") (pintype "passive"))
    )
    (net (code "93") (name "VCC") (class "Default")
      (node (ref "C11") (pin "1") (pinfunction "+_1") (pintype "passive"))
      (node (ref "C1117") (pin "2") (pintype "passive"))
      (node (ref "C1118") (pin "2") (pintype "passive"))
      (node (ref "C12") (pin "2") (pintype "passive"))
      (node (ref "C13") (pin "2") (pintype "passive"))
      (node (ref "P113") (pin "3") (pinfunction "3_3") (pintype "passive"))
      (node (ref "P9") (pin "2") (pinfunction "2_2") (pintype "passive"))
      (node (ref "R11") (pin "1") (pinfunction "1_1") (pintype "passive"))
      (node (ref "R6") (pin "1") (pinfunction "1_1") (pintype "passive"))
      (node (ref "U132") (pin "10") (pinfunction "VCC_10") (pintype "power_in"))
      (node (ref "U132") (pin "30") (pinfunction "AVCC_30") (pintype "power_in"))
      (node (ref "U132") (pin "32") (pinfunction "AREF_32") (pintype "passive"))
      (node (ref "U5") (pin "1") (pinfunction "1_1") (pintype "passive"))
      (node (ref "U6") (pin "3") (pinfunction "+5V_3") (pintype "power_in"))
    )
  )
)
